# Mini-Keyboard.net
KiCad netlist of a schematic drawn in EasyEDA Pro
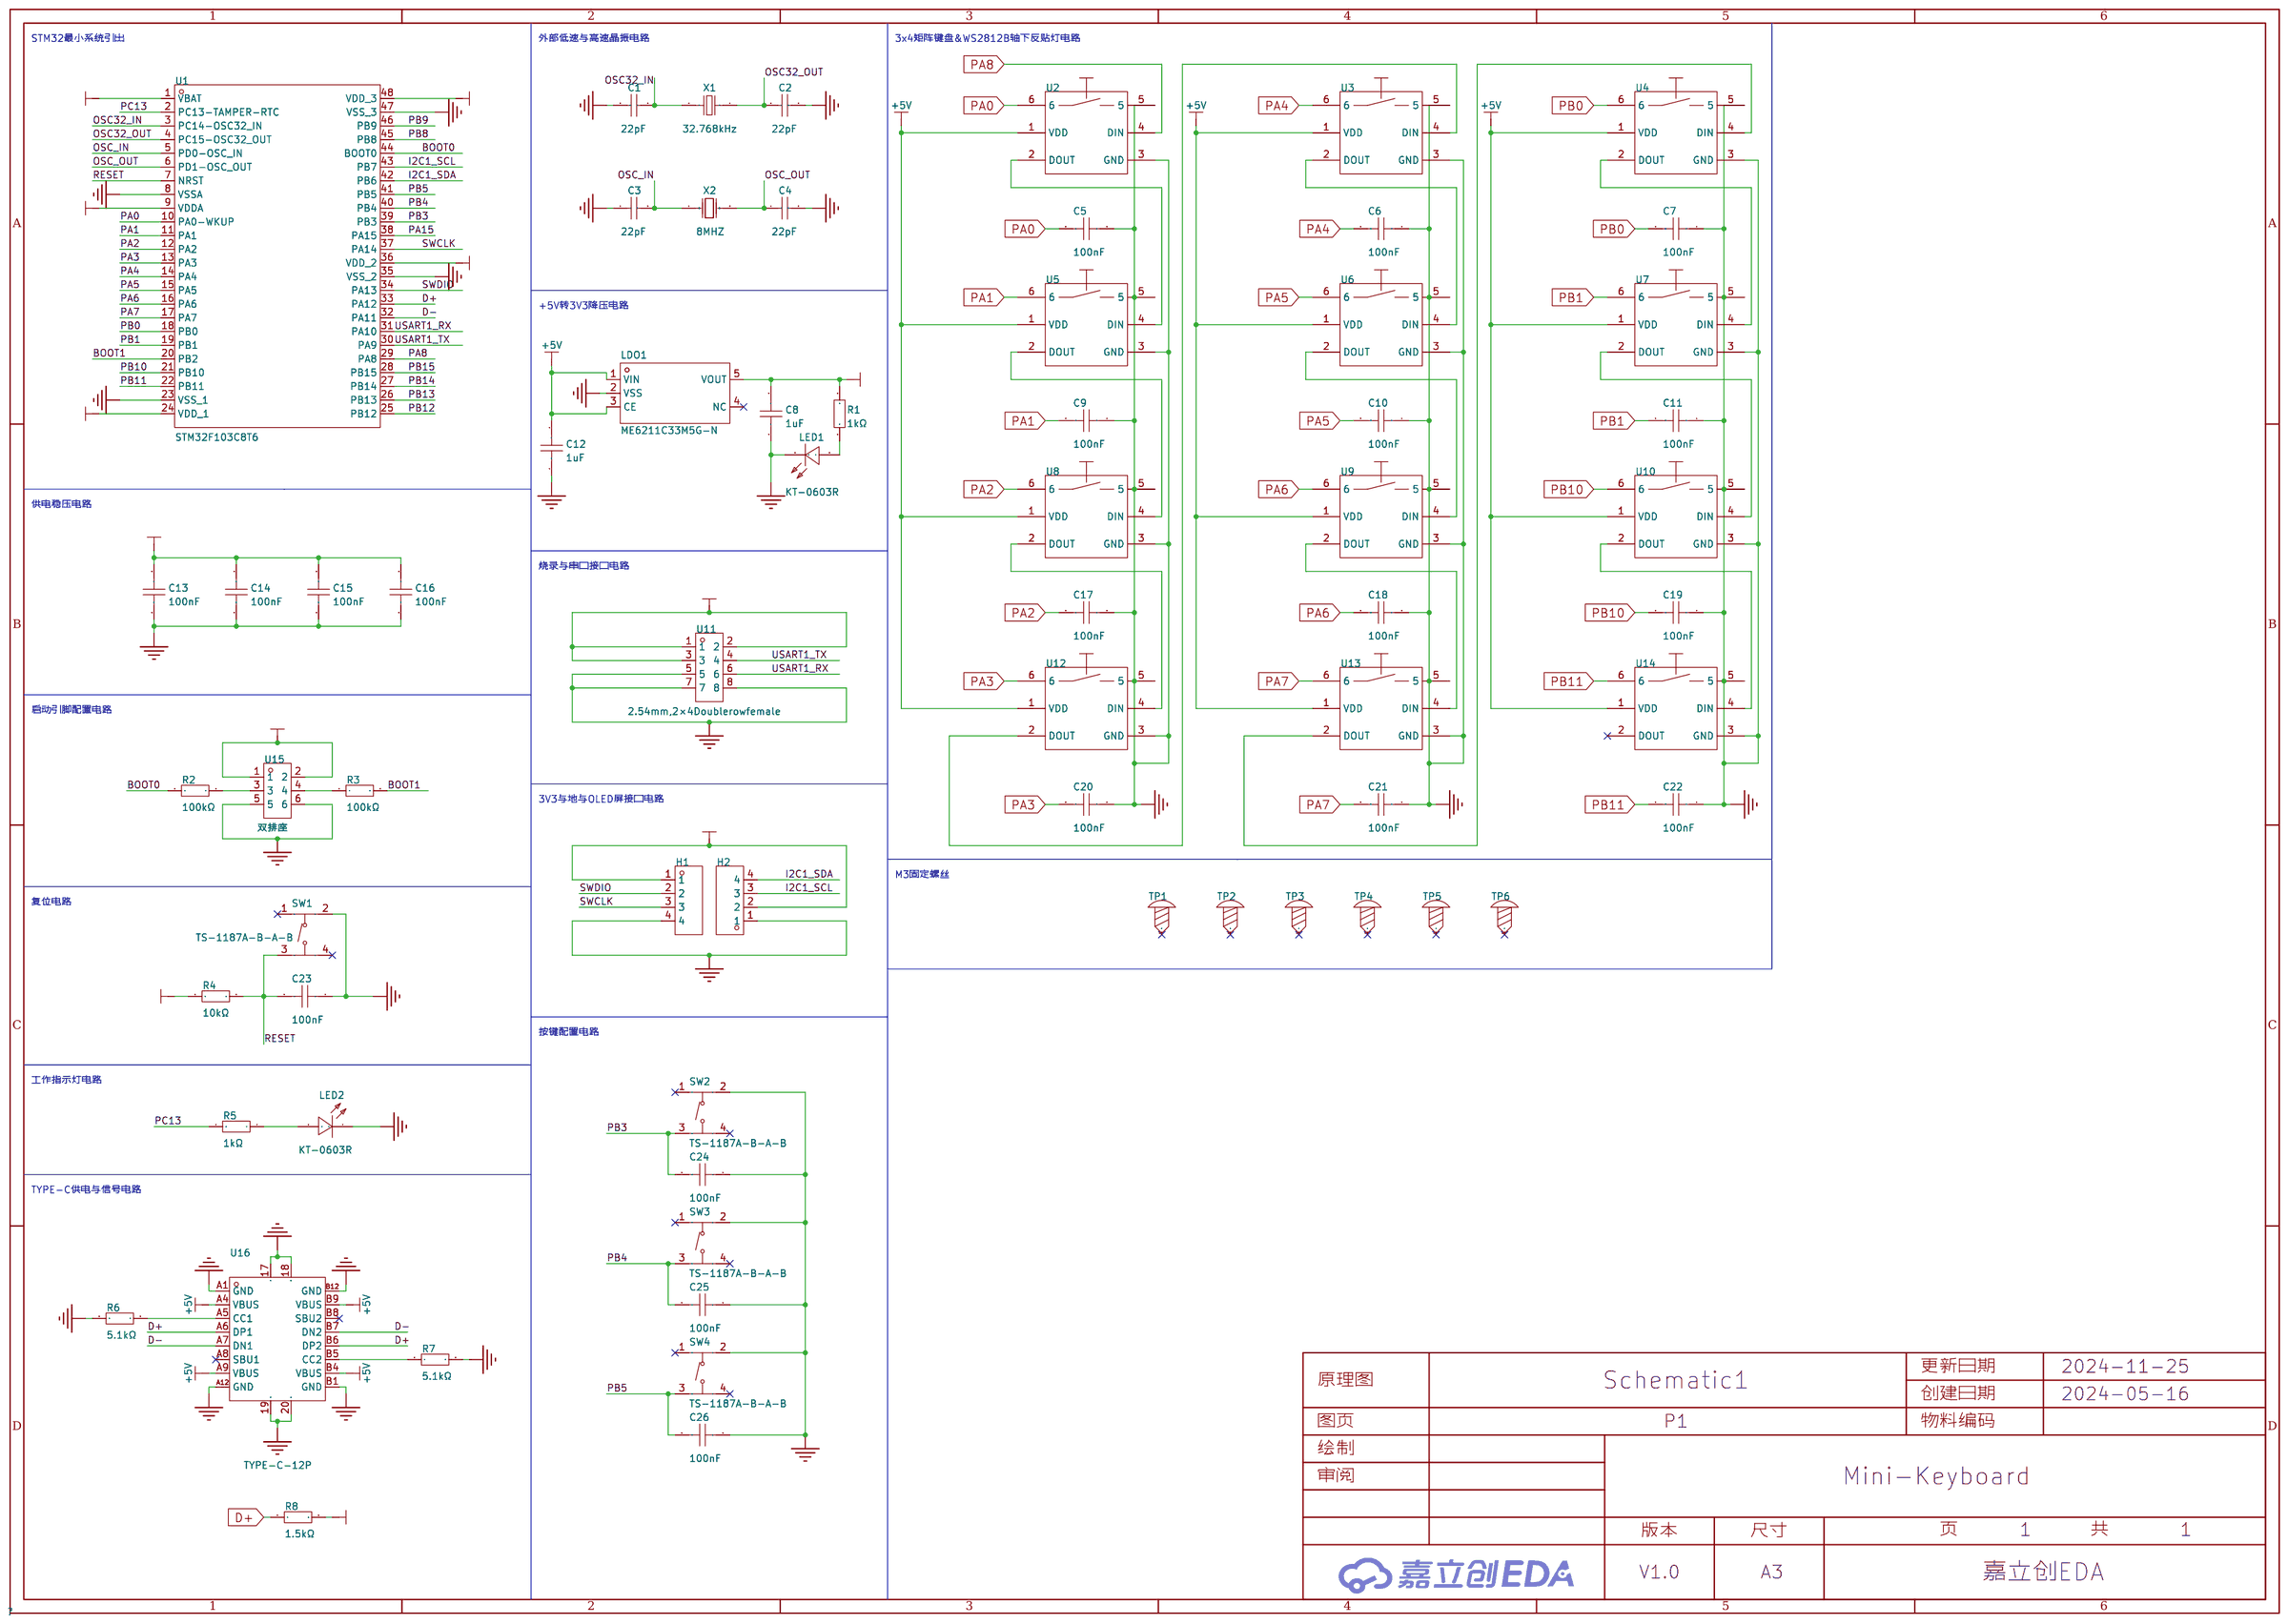
[diagram p0: schematic sheet]

(export (version "E")
  (design (tool "Eeschema 10.0.6"))
  (components
    (comp (ref "C1")
      (value "22pF")
      (footprint "easyedapro:C0603")
      (description "容值:22pF;精度:±5%;额定电压:50V;材质(温度系数):C0G;")
      (fields
        (field (name "Manufacturer Part") "CL10C220JB8NNNC")
        (field (name "Manufacturer") "SAMSUNG(三星)")
      )
      (libsource (lib "easyedapro") (part "CL10C220JB8NNNC"))
    )
    (comp (ref "C2")
      (value "22pF")
      (footprint "easyedapro:C0603")
      (description "容值:22pF;精度:±5%;额定电压:50V;材质(温度系数):C0G;")
      (fields
        (field (name "Manufacturer Part") "CL10C220JB8NNNC")
        (field (name "Manufacturer") "SAMSUNG(三星)")
      )
      (libsource (lib "easyedapro") (part "CL10C220JB8NNNC"))
    )
    (comp (ref "C3")
      (value "22pF")
      (footprint "easyedapro:C0603")
      (description "容值:22pF;精度:±5%;额定电压:50V;材质(温度系数):C0G;")
      (fields
        (field (name "Manufacturer Part") "CL10C220JB8NNNC")
        (field (name "Manufacturer") "SAMSUNG(三星)")
      )
      (libsource (lib "easyedapro") (part "CL10C220JB8NNNC"))
    )
    (comp (ref "C4")
      (value "22pF")
      (footprint "easyedapro:C0603")
      (description "容值:22pF;精度:±5%;额定电压:50V;材质(温度系数):C0G;")
      (fields
        (field (name "Manufacturer Part") "CL10C220JB8NNNC")
        (field (name "Manufacturer") "SAMSUNG(三星)")
      )
      (libsource (lib "easyedapro") (part "CL10C220JB8NNNC"))
    )
    (comp (ref "C5")
      (value "100nF")
      (footprint "easyedapro:C0603")
      (description "容值:100nF;精度:±10%;额定电压:50V;材质(温度系数):X7R;")
      (fields
        (field (name "Manufacturer Part") "CC0603KRX7R9BB104")
        (field (name "Manufacturer") "YAGEO(国巨)")
      )
      (libsource (lib "easyedapro") (part "CC0603KRX7R9BB104"))
    )
    (comp (ref "C6")
      (value "100nF")
      (footprint "easyedapro:C0603")
      (description "容值:100nF;精度:±10%;额定电压:50V;材质(温度系数):X7R;")
      (fields
        (field (name "Manufacturer Part") "CC0603KRX7R9BB104")
        (field (name "Manufacturer") "YAGEO(国巨)")
      )
      (libsource (lib "easyedapro") (part "CC0603KRX7R9BB104"))
    )
    (comp (ref "C7")
      (value "100nF")
      (footprint "easyedapro:C0603")
      (description "容值:100nF;精度:±10%;额定电压:50V;材质(温度系数):X7R;")
      (fields
        (field (name "Manufacturer Part") "CC0603KRX7R9BB104")
        (field (name "Manufacturer") "YAGEO(国巨)")
      )
      (libsource (lib "easyedapro") (part "CC0603KRX7R9BB104"))
    )
    (comp (ref "C8")
      (value "1uF")
      (footprint "easyedapro:C0603")
      (description "容值:1uF;精度:±10%;额定电压:50V;材质(温度系数):X5R;")
      (fields
        (field (name "Manufacturer Part") "CL10A105KB8NNNC")
        (field (name "Manufacturer") "SAMSUNG(三星)")
      )
      (libsource (lib "easyedapro") (part "CL10A105KB8NNNC"))
    )
    (comp (ref "C9")
      (value "100nF")
      (footprint "easyedapro:C0603")
      (description "容值:100nF;精度:±10%;额定电压:50V;材质(温度系数):X7R;")
      (fields
        (field (name "Manufacturer Part") "CC0603KRX7R9BB104")
        (field (name "Manufacturer") "YAGEO(国巨)")
      )
      (libsource (lib "easyedapro") (part "CC0603KRX7R9BB104"))
    )
    (comp (ref "C10")
      (value "100nF")
      (footprint "easyedapro:C0603")
      (description "容值:100nF;精度:±10%;额定电压:50V;材质(温度系数):X7R;")
      (fields
        (field (name "Manufacturer Part") "CC0603KRX7R9BB104")
        (field (name "Manufacturer") "YAGEO(国巨)")
      )
      (libsource (lib "easyedapro") (part "CC0603KRX7R9BB104"))
    )
    (comp (ref "C11")
      (value "100nF")
      (footprint "easyedapro:C0603")
      (description "容值:100nF;精度:±10%;额定电压:50V;材质(温度系数):X7R;")
      (fields
        (field (name "Manufacturer Part") "CC0603KRX7R9BB104")
        (field (name "Manufacturer") "YAGEO(国巨)")
      )
      (libsource (lib "easyedapro") (part "CC0603KRX7R9BB104"))
    )
    (comp (ref "C12")
      (value "1uF")
      (footprint "easyedapro:C0603")
      (description "容值:1uF;精度:±10%;额定电压:50V;材质(温度系数):X5R;")
      (fields
        (field (name "Manufacturer Part") "CL10A105KB8NNNC")
        (field (name "Manufacturer") "SAMSUNG(三星)")
      )
      (libsource (lib "easyedapro") (part "CL10A105KB8NNNC"))
    )
    (comp (ref "C13")
      (value "100nF")
      (footprint "easyedapro:C0603")
      (description "容值:100nF;精度:±10%;额定电压:50V;材质(温度系数):X7R;")
      (fields
        (field (name "Manufacturer Part") "CC0603KRX7R9BB104")
        (field (name "Manufacturer") "YAGEO(国巨)")
      )
      (libsource (lib "easyedapro") (part "CC0603KRX7R9BB104"))
    )
    (comp (ref "C14")
      (value "100nF")
      (footprint "easyedapro:C0603")
      (description "容值:100nF;精度:±10%;额定电压:50V;材质(温度系数):X7R;")
      (fields
        (field (name "Manufacturer Part") "CC0603KRX7R9BB104")
        (field (name "Manufacturer") "YAGEO(国巨)")
      )
      (libsource (lib "easyedapro") (part "CC0603KRX7R9BB104"))
    )
    (comp (ref "C15")
      (value "100nF")
      (footprint "easyedapro:C0603")
      (description "容值:100nF;精度:±10%;额定电压:50V;材质(温度系数):X7R;")
      (fields
        (field (name "Manufacturer Part") "CC0603KRX7R9BB104")
        (field (name "Manufacturer") "YAGEO(国巨)")
      )
      (libsource (lib "easyedapro") (part "CC0603KRX7R9BB104"))
    )
    (comp (ref "C16")
      (value "100nF")
      (footprint "easyedapro:C0603")
      (description "容值:100nF;精度:±10%;额定电压:50V;材质(温度系数):X7R;")
      (fields
        (field (name "Manufacturer Part") "CC0603KRX7R9BB104")
        (field (name "Manufacturer") "YAGEO(国巨)")
      )
      (libsource (lib "easyedapro") (part "CC0603KRX7R9BB104"))
    )
    (comp (ref "C17")
      (value "100nF")
      (footprint "easyedapro:C0603")
      (description "容值:100nF;精度:±10%;额定电压:50V;材质(温度系数):X7R;")
      (fields
        (field (name "Manufacturer Part") "CC0603KRX7R9BB104")
        (field (name "Manufacturer") "YAGEO(国巨)")
      )
      (libsource (lib "easyedapro") (part "CC0603KRX7R9BB104"))
    )
    (comp (ref "C18")
      (value "100nF")
      (footprint "easyedapro:C0603")
      (description "容值:100nF;精度:±10%;额定电压:50V;材质(温度系数):X7R;")
      (fields
        (field (name "Manufacturer Part") "CC0603KRX7R9BB104")
        (field (name "Manufacturer") "YAGEO(国巨)")
      )
      (libsource (lib "easyedapro") (part "CC0603KRX7R9BB104"))
    )
    (comp (ref "C19")
      (value "100nF")
      (footprint "easyedapro:C0603")
      (description "容值:100nF;精度:±10%;额定电压:50V;材质(温度系数):X7R;")
      (fields
        (field (name "Manufacturer Part") "CC0603KRX7R9BB104")
        (field (name "Manufacturer") "YAGEO(国巨)")
      )
      (libsource (lib "easyedapro") (part "CC0603KRX7R9BB104"))
    )
    (comp (ref "C20")
      (value "100nF")
      (footprint "easyedapro:C0603")
      (description "容值:100nF;精度:±10%;额定电压:50V;材质(温度系数):X7R;")
      (fields
        (field (name "Manufacturer Part") "CC0603KRX7R9BB104")
        (field (name "Manufacturer") "YAGEO(国巨)")
      )
      (libsource (lib "easyedapro") (part "CC0603KRX7R9BB104"))
    )
    (comp (ref "C21")
      (value "100nF")
      (footprint "easyedapro:C0603")
      (description "容值:100nF;精度:±10%;额定电压:50V;材质(温度系数):X7R;")
      (fields
        (field (name "Manufacturer Part") "CC0603KRX7R9BB104")
        (field (name "Manufacturer") "YAGEO(国巨)")
      )
      (libsource (lib "easyedapro") (part "CC0603KRX7R9BB104"))
    )
    (comp (ref "C22")
      (value "100nF")
      (footprint "easyedapro:C0603")
      (description "容值:100nF;精度:±10%;额定电压:50V;材质(温度系数):X7R;")
      (fields
        (field (name "Manufacturer Part") "CC0603KRX7R9BB104")
        (field (name "Manufacturer") "YAGEO(国巨)")
      )
      (libsource (lib "easyedapro") (part "CC0603KRX7R9BB104"))
    )
    (comp (ref "C23")
      (value "100nF")
      (footprint "easyedapro:C0603")
      (description "容值:100nF;精度:±10%;额定电压:50V;材质(温度系数):X7R;")
      (fields
        (field (name "Manufacturer Part") "CC0603KRX7R9BB104")
        (field (name "Manufacturer") "YAGEO(国巨)")
      )
      (libsource (lib "easyedapro") (part "CC0603KRX7R9BB104"))
    )
    (comp (ref "C24")
      (value "100nF")
      (footprint "easyedapro:C0603")
      (description "容值:100nF;精度:±10%;额定电压:50V;材质(温度系数):X7R;")
      (fields
        (field (name "Manufacturer Part") "CC0603KRX7R9BB104")
        (field (name "Manufacturer") "YAGEO(国巨)")
      )
      (libsource (lib "easyedapro") (part "CC0603KRX7R9BB104"))
    )
    (comp (ref "C25")
      (value "100nF")
      (footprint "easyedapro:C0603")
      (description "容值:100nF;精度:±10%;额定电压:50V;材质(温度系数):X7R;")
      (fields
        (field (name "Manufacturer Part") "CC0603KRX7R9BB104")
        (field (name "Manufacturer") "YAGEO(国巨)")
      )
      (libsource (lib "easyedapro") (part "CC0603KRX7R9BB104"))
    )
    (comp (ref "C26")
      (value "100nF")
      (footprint "easyedapro:C0603")
      (description "容值:100nF;精度:±10%;额定电压:50V;材质(温度系数):X7R;")
      (fields
        (field (name "Manufacturer Part") "CC0603KRX7R9BB104")
        (field (name "Manufacturer") "YAGEO(国巨)")
      )
      (libsource (lib "easyedapro") (part "CC0603KRX7R9BB104"))
    )
    (comp (ref "H1")
      (value "~")
      (footprint "easyedapro:hdr-th_4p-p2.54-v-f")
      (libsource (lib "easyedapro") (part "2.54-1*4P母"))
    )
    (comp (ref "H2")
      (value "~")
      (footprint "easyedapro:hdr-th_4p-p2.54-v-f")
      (libsource (lib "easyedapro") (part "2.54-1*4P母"))
    )
    (comp (ref "LDO1")
      (value "ME6211C33M5G-N")
      (footprint "easyedapro:SOT-23-5_L3.0-W1.7-P0.95-LS2.8-BL")
      (description "输出类型:固定;最大输入电压:6V;输出电压:3.3V;最大输出电流:500mA;电源纹波抑制比(PSRR):70dB;输出极性:正极;")
      (fields (field (name "Manufacturer") "MICRONE(南京微盟)"))
      (libsource (lib "easyedapro") (part "ME6211C33M5G-N"))
    )
    (comp (ref "LED1")
      (value "KT-0603R")
      (footprint "easyedapro:LED0603-RD")
      (description "发光颜色:红色;功率:-;正向电流:-;主波长:-;二极管配置:-;透镜颜色:-;色温:-;发光角度:-;载带方式:-;工作温度:-40°C~+85°C;")
      (fields (field (name "Manufacturer") "KENTO"))
      (libsource (lib "easyedapro") (part "kt-0603r"))
    )
    (comp (ref "LED2")
      (value "KT-0603R")
      (footprint "easyedapro:LED0603-RD")
      (description "发光颜色:红色;功率:-;正向电流:-;主波长:-;二极管配置:-;透镜颜色:-;色温:-;发光角度:-;载带方式:-;工作温度:-40°C~+85°C;")
      (fields (field (name "Manufacturer") "KENTO"))
      (libsource (lib "easyedapro") (part "kt-0603r"))
    )
    (comp (ref "R1")
      (value "1kΩ")
      (footprint "easyedapro:R0603")
      (description "电阻类型:厚膜电阻;阻值:1kΩ;精度:±1%;功率:100mW;最大工作电压:75V;温度系数:±100ppm/°C;")
      (fields
        (field (name "Manufacturer Part") "0603WAF1001T5E")
        (field (name "Manufacturer") "UNI-ROYAL(厚声)")
      )
      (libsource (lib "easyedapro") (part "0603WAF1001T5E"))
    )
    (comp (ref "R2")
      (value "100kΩ")
      (footprint "easyedapro:R0603")
      (description "电阻类型:厚膜电阻;阻值:100kΩ;精度:±1%;功率:100mW;最大工作电压:75V;温度系数:±100ppm/°C;")
      (fields
        (field (name "Manufacturer Part") "0603WAF1003T5E")
        (field (name "Manufacturer") "UNI-ROYAL(厚声)")
      )
      (libsource (lib "easyedapro") (part "0603WAF1003T5E"))
    )
    (comp (ref "R3")
      (value "100kΩ")
      (footprint "easyedapro:R0603")
      (description "电阻类型:厚膜电阻;阻值:100kΩ;精度:±1%;功率:100mW;最大工作电压:75V;温度系数:±100ppm/°C;")
      (fields
        (field (name "Manufacturer Part") "0603WAF1003T5E")
        (field (name "Manufacturer") "UNI-ROYAL(厚声)")
      )
      (libsource (lib "easyedapro") (part "0603WAF1003T5E"))
    )
    (comp (ref "R4")
      (value "10kΩ")
      (footprint "easyedapro:R0603")
      (description "电阻类型:厚膜电阻;阻值:10kΩ;精度:±1%;功率:100mW;最大工作电压:75V;温度系数:±100ppm/°C;")
      (fields
        (field (name "Manufacturer Part") "0603WAF1002T5E")
        (field (name "Manufacturer") "UNI-ROYAL(厚声)")
      )
      (libsource (lib "easyedapro") (part "0603WAF1002T5E"))
    )
    (comp (ref "R5")
      (value "1kΩ")
      (footprint "easyedapro:R0603")
      (description "电阻类型:厚膜电阻;阻值:1kΩ;精度:±1%;功率:100mW;最大工作电压:75V;温度系数:±100ppm/°C;")
      (fields
        (field (name "Manufacturer Part") "0603WAF1001T5E")
        (field (name "Manufacturer") "UNI-ROYAL(厚声)")
      )
      (libsource (lib "easyedapro") (part "0603WAF1001T5E"))
    )
    (comp (ref "R6")
      (value "5.1kΩ")
      (footprint "easyedapro:R0603")
      (description "电阻类型:厚膜电阻;阻值:5.1kΩ;精度:±1%;功率:100mW;最大工作电压:75V;温度系数:±100ppm/°C;")
      (fields
        (field (name "Manufacturer Part") "0603WAF5101T5E")
        (field (name "Manufacturer") "UNI-ROYAL(厚声)")
      )
      (libsource (lib "easyedapro") (part "0603WAF5101T5E"))
    )
    (comp (ref "R7")
      (value "5.1kΩ")
      (footprint "easyedapro:R0603")
      (description "电阻类型:厚膜电阻;阻值:5.1kΩ;精度:±1%;功率:100mW;最大工作电压:75V;温度系数:±100ppm/°C;")
      (fields
        (field (name "Manufacturer Part") "0603WAF5101T5E")
        (field (name "Manufacturer") "UNI-ROYAL(厚声)")
      )
      (libsource (lib "easyedapro") (part "0603WAF5101T5E"))
    )
    (comp (ref "R8")
      (value "1.5kΩ")
      (footprint "easyedapro:R0603")
      (description "电阻类型:厚膜电阻;阻值:1.5kΩ;精度:±1%;功率:100mW;最大工作电压:75V;温度系数:±100ppm/°C;")
      (fields
        (field (name "Manufacturer Part") "0603WAF1501T5E")
        (field (name "Manufacturer") "UNI-ROYAL(厚声)")
      )
      (libsource (lib "easyedapro") (part "0603WAF1501T5E"))
    )
    (comp (ref "SW1")
      (value "TS-1187A-B-A-B")
      (footprint "easyedapro:SW-SMD_4P-L5.1-W5.1-P3.70-LS6.5-TL-2")
      (fields (field (name "Manufacturer") "XKB Connectivity(中国星坤)"))
      (libsource (lib "easyedapro") (part "TS-1187A-B-A-B"))
    )
    (comp (ref "SW2")
      (value "TS-1187A-B-A-B")
      (footprint "easyedapro:SW-SMD_4P-L5.1-W5.1-P3.70-LS6.5-TL-2")
      (fields (field (name "Manufacturer") "XKB Connectivity(中国星坤)"))
      (libsource (lib "easyedapro") (part "TS-1187A-B-A-B"))
    )
    (comp (ref "SW3")
      (value "TS-1187A-B-A-B")
      (footprint "easyedapro:SW-SMD_4P-L5.1-W5.1-P3.70-LS6.5-TL-2")
      (fields (field (name "Manufacturer") "XKB Connectivity(中国星坤)"))
      (libsource (lib "easyedapro") (part "TS-1187A-B-A-B"))
    )
    (comp (ref "SW4")
      (value "TS-1187A-B-A-B")
      (footprint "easyedapro:SW-SMD_4P-L5.1-W5.1-P3.70-LS6.5-TL-2")
      (fields (field (name "Manufacturer") "XKB Connectivity(中国星坤)"))
      (libsource (lib "easyedapro") (part "TS-1187A-B-A-B"))
    )
    (comp (ref "TP1") (value "~") (footprint "easyedapro:M3螺丝") (libsource (lib "easyedapro") (part "螺丝孔")))
    (comp (ref "TP2") (value "~") (footprint "easyedapro:M3螺丝") (libsource (lib "easyedapro") (part "螺丝孔")))
    (comp (ref "TP3") (value "~") (footprint "easyedapro:M3螺丝") (libsource (lib "easyedapro") (part "螺丝孔")))
    (comp (ref "TP4") (value "~") (footprint "easyedapro:M3螺丝") (libsource (lib "easyedapro") (part "螺丝孔")))
    (comp (ref "TP5") (value "~") (footprint "easyedapro:M3螺丝") (libsource (lib "easyedapro") (part "螺丝孔")))
    (comp (ref "TP6") (value "~") (footprint "easyedapro:M3螺丝") (libsource (lib "easyedapro") (part "螺丝孔")))
    (comp (ref "U1")
      (value "STM32F103C8T6")
      (footprint "easyedapro:LQFP-48_L7.0-W7.0-P0.50-LS9.0-BL")
      (description "CPU内核:ARM-M3;程序存储容量:64KB;RAM总容量:20KB;GPIO端口数量:37;工作电压范围:2V~3.6V;CPU最大主频:72MHz;程序存储器类型:FLASH;")
      (fields (field (name "Manufacturer") "ST(意法半导体)"))
      (libsource (lib "easyedapro") (part "stm32f103c8t6"))
    )
    (comp (ref "U2")
      (value "~")
      (footprint "easyedapro:KAILH_WS2182B_3528 反贴")
      (libsource (lib "easyedapro") (part "KAILH_WS2182B_3528 反贴"))
    )
    (comp (ref "U3")
      (value "~")
      (footprint "easyedapro:KAILH_WS2182B_3528 反贴")
      (libsource (lib "easyedapro") (part "KAILH_WS2182B_3528 反贴"))
    )
    (comp (ref "U4")
      (value "~")
      (footprint "easyedapro:KAILH_WS2182B_3528 反贴")
      (libsource (lib "easyedapro") (part "KAILH_WS2182B_3528 反贴"))
    )
    (comp (ref "U5")
      (value "~")
      (footprint "easyedapro:KAILH_WS2182B_3528 反贴")
      (libsource (lib "easyedapro") (part "KAILH_WS2182B_3528 反贴"))
    )
    (comp (ref "U6")
      (value "~")
      (footprint "easyedapro:KAILH_WS2182B_3528 反贴")
      (libsource (lib "easyedapro") (part "KAILH_WS2182B_3528 反贴"))
    )
    (comp (ref "U7")
      (value "~")
      (footprint "easyedapro:KAILH_WS2182B_3528 反贴")
      (libsource (lib "easyedapro") (part "KAILH_WS2182B_3528 反贴"))
    )
    (comp (ref "U8")
      (value "~")
      (footprint "easyedapro:KAILH_WS2182B_3528 反贴")
      (libsource (lib "easyedapro") (part "KAILH_WS2182B_3528 反贴"))
    )
    (comp (ref "U9")
      (value "~")
      (footprint "easyedapro:KAILH_WS2182B_3528 反贴")
      (libsource (lib "easyedapro") (part "KAILH_WS2182B_3528 反贴"))
    )
    (comp (ref "U10")
      (value "~")
      (footprint "easyedapro:KAILH_WS2182B_3528 反贴")
      (libsource (lib "easyedapro") (part "KAILH_WS2182B_3528 反贴"))
    )
    (comp (ref "U11")
      (value "2.54mm,2×4Doublerowfemale")
      (footprint "easyedapro:HDR-TH_8P-P2.54-V-F-R2-C4-S2.54-1")
      (libsource (lib "easyedapro") (part "2.54MM,2×4DOUBLEROWFEMALE"))
    )
    (comp (ref "U12")
      (value "~")
      (footprint "easyedapro:KAILH_WS2182B_3528 反贴")
      (libsource (lib "easyedapro") (part "KAILH_WS2182B_3528 反贴"))
    )
    (comp (ref "U13")
      (value "~")
      (footprint "easyedapro:KAILH_WS2182B_3528 反贴")
      (libsource (lib "easyedapro") (part "KAILH_WS2182B_3528 反贴"))
    )
    (comp (ref "U14")
      (value "~")
      (footprint "easyedapro:KAILH_WS2182B_3528 反贴")
      (libsource (lib "easyedapro") (part "KAILH_WS2182B_3528 反贴"))
    )
    (comp (ref "U15")
      (value "双排座")
      (footprint "easyedapro:HDR-TH_6P-P2.54-V-F-R2-C3-S2.54")
      (libsource (lib "easyedapro") (part "双排座"))
    )
    (comp (ref "U16")
      (value "TYPE-C-12P")
      (footprint "easyedapro:USB-SMD_TYPE-C16PIN")
      (libsource (lib "easyedapro") (part "TYPE-C-12P"))
    )
    (comp (ref "X1")
      (value "32.768kHz")
      (footprint "easyedapro:CRYSTAL-SMD_L3.2-W1.5-1")
      (description "晶振类型:贴片晶振;频率:32.768kHz;常温频差:±20ppm;外接负载电容:12.5pF;频率稳定度(全温):±20ppm;")
      (fields
        (field (name "Manufacturer Part") "FC31M2-32.768-NTLLLDT")
        (field (name "Manufacturer") "HCI(杭晶)")
      )
      (libsource (lib "easyedapro") (part "FC31M2-32.768-NTLLLDT"))
    )
    (comp (ref "X2")
      (value "8MHZ")
      (footprint "easyedapro:HC-49S_L11.5-W5.0-P4.88")
      (libsource (lib "easyedapro") (part "8MHZ_C9900021358"))
    )
  )
  (nets
    (net (code "1") (name "+5V") (class "Default")
      (node (ref "C12") (pin "2") (pinfunction "2_2") (pintype "unspecified"))
      (node (ref "LDO1") (pin "1") (pinfunction "VIN_1") (pintype "input"))
      (node (ref "LDO1") (pin "3") (pinfunction "CE_3") (pintype "input"))
      (node (ref "U10") (pin "1") (pinfunction "VDD_1") (pintype "input"))
      (node (ref "U12") (pin "1") (pinfunction "VDD_1") (pintype "input"))
      (node (ref "U13") (pin "1") (pinfunction "VDD_1") (pintype "input"))
      (node (ref "U14") (pin "1") (pinfunction "VDD_1") (pintype "input"))
      (node (ref "U16") (pin "A4") (pinfunction "VBUS_A4") (pintype "unspecified"))
      (node (ref "U16") (pin "A9") (pinfunction "VBUS_A9") (pintype "unspecified"))
      (node (ref "U16") (pin "B4") (pinfunction "VBUS_B4") (pintype "unspecified"))
      (node (ref "U16") (pin "B9") (pinfunction "VBUS_B9") (pintype "unspecified"))
      (node (ref "U2") (pin "1") (pinfunction "VDD_1") (pintype "input"))
      (node (ref "U3") (pin "1") (pinfunction "VDD_1") (pintype "input"))
      (node (ref "U4") (pin "1") (pinfunction "VDD_1") (pintype "input"))
      (node (ref "U5") (pin "1") (pinfunction "VDD_1") (pintype "input"))
      (node (ref "U6") (pin "1") (pinfunction "VDD_1") (pintype "input"))
      (node (ref "U7") (pin "1") (pinfunction "VDD_1") (pintype "input"))
      (node (ref "U8") (pin "1") (pinfunction "VDD_1") (pintype "input"))
      (node (ref "U9") (pin "1") (pinfunction "VDD_1") (pintype "input"))
    )
    (net (code "2") (name "/BOOT0") (class "Default")
      (node (ref "R2") (pin "1") (pinfunction "1_1") (pintype "input"))
      (node (ref "U1") (pin "44") (pinfunction "BOOT0_44") (pintype "unspecified"))
    )
    (net (code "3") (name "/BOOT1") (class "Default")
      (node (ref "R3") (pin "2") (pinfunction "2_2") (pintype "input"))
      (node (ref "U1") (pin "20") (pinfunction "PB2_20") (pintype "unspecified"))
    )
    (net (code "4") (name "/D-") (class "Default")
      (node (ref "U1") (pin "32") (pinfunction "PA11_32") (pintype "unspecified"))
      (node (ref "U16") (pin "A7") (pinfunction "DN1_A7") (pintype "unspecified"))
      (node (ref "U16") (pin "B7") (pinfunction "DN2_B7") (pintype "unspecified"))
    )
    (net (code "5") (name "/I2C1_SCL") (class "Default")
      (node (ref "H2") (pin "3") (pinfunction "3_3") (pintype "unspecified"))
      (node (ref "U1") (pin "43") (pinfunction "PB7_43") (pintype "unspecified"))
    )
    (net (code "6") (name "/I2C1_SDA") (class "Default")
      (node (ref "H2") (pin "4") (pinfunction "4_4") (pintype "unspecified"))
      (node (ref "U1") (pin "42") (pinfunction "PB6_42") (pintype "unspecified"))
    )
    (net (code "7") (name "/OSC32_IN") (class "Default")
      (node (ref "C1") (pin "2") (pinfunction "2_2") (pintype "input"))
      (node (ref "U1") (pin "3") (pinfunction "PC14-OSC32_IN_3") (pintype "unspecified"))
      (node (ref "X1") (pin "2") (pinfunction "2_2") (pintype "unspecified"))
    )
    (net (code "8") (name "/OSC32_OUT") (class "Default")
      (node (ref "C2") (pin "2") (pinfunction "2_2") (pintype "input"))
      (node (ref "U1") (pin "4") (pinfunction "PC15-OSC32_OUT_4") (pintype "unspecified"))
      (node (ref "X1") (pin "1") (pinfunction "1_1") (pintype "unspecified"))
    )
    (net (code "9") (name "/OSC_IN") (class "Default")
      (node (ref "C3") (pin "2") (pinfunction "2_2") (pintype "input"))
      (node (ref "U1") (pin "5") (pinfunction "PD0-OSC_IN_5") (pintype "unspecified"))
      (node (ref "X2") (pin "1") (pinfunction "OSC1_1") (pintype "input"))
    )
    (net (code "10") (name "/OSC_OUT") (class "Default")
      (node (ref "C4") (pin "1") (pinfunction "1_1") (pintype "input"))
      (node (ref "U1") (pin "6") (pinfunction "PD1-OSC_OUT_6") (pintype "unspecified"))
      (node (ref "X2") (pin "2") (pinfunction "OSC2_2") (pintype "input"))
    )
    (net (code "11") (name "/PA15") (class "Default")
      (node (ref "U1") (pin "38") (pinfunction "PA15_38") (pintype "unspecified"))
    )
    (net (code "12") (name "/PB3") (class "Default")
      (node (ref "C24") (pin "2") (pinfunction "2_2") (pintype "unspecified"))
      (node (ref "SW2") (pin "3") (pinfunction "C_3") (pintype "unspecified"))
      (node (ref "U1") (pin "39") (pinfunction "PB3_39") (pintype "unspecified"))
    )
    (net (code "13") (name "/PB4") (class "Default")
      (node (ref "C25") (pin "2") (pinfunction "2_2") (pintype "unspecified"))
      (node (ref "SW3") (pin "3") (pinfunction "C_3") (pintype "unspecified"))
      (node (ref "U1") (pin "40") (pinfunction "PB4_40") (pintype "unspecified"))
    )
    (net (code "14") (name "/PB5") (class "Default")
      (node (ref "C26") (pin "2") (pinfunction "2_2") (pintype "unspecified"))
      (node (ref "SW4") (pin "3") (pinfunction "C_3") (pintype "unspecified"))
      (node (ref "U1") (pin "41") (pinfunction "PB5_41") (pintype "unspecified"))
    )
    (net (code "15") (name "/PB8") (class "Default")
      (node (ref "U1") (pin "45") (pinfunction "PB8_45") (pintype "unspecified"))
    )
    (net (code "16") (name "/PB9") (class "Default")
      (node (ref "U1") (pin "46") (pinfunction "PB9_46") (pintype "unspecified"))
    )
    (net (code "17") (name "/PB12") (class "Default")
      (node (ref "U1") (pin "25") (pinfunction "PB12_25") (pintype "unspecified"))
    )
    (net (code "18") (name "/PB13") (class "Default")
      (node (ref "U1") (pin "26") (pinfunction "PB13_26") (pintype "unspecified"))
    )
    (net (code "19") (name "/PB14") (class "Default")
      (node (ref "U1") (pin "27") (pinfunction "PB14_27") (pintype "unspecified"))
    )
    (net (code "20") (name "/PB15") (class "Default")
      (node (ref "U1") (pin "28") (pinfunction "PB15_28") (pintype "unspecified"))
    )
    (net (code "21") (name "/PC13") (class "Default")
      (node (ref "R5") (pin "2") (pinfunction "2_2") (pintype "input"))
      (node (ref "U1") (pin "2") (pinfunction "PC13-TAMPER-RTC_2") (pintype "unspecified"))
    )
    (net (code "22") (name "/RESET") (class "Default")
      (node (ref "C23") (pin "2") (pinfunction "2_2") (pintype "unspecified"))
      (node (ref "R4") (pin "1") (pinfunction "1_1") (pintype "input"))
      (node (ref "SW1") (pin "3") (pinfunction "C_3") (pintype "unspecified"))
      (node (ref "U1") (pin "7") (pinfunction "NRST_7") (pintype "unspecified"))
    )
    (net (code "23") (name "/SWCLK") (class "Default")
      (node (ref "H1") (pin "3") (pinfunction "3_3") (pintype "unspecified"))
      (node (ref "U1") (pin "37") (pinfunction "PA14_37") (pintype "unspecified"))
    )
    (net (code "24") (name "/SWDIO") (class "Default")
      (node (ref "H1") (pin "2") (pinfunction "2_2") (pintype "unspecified"))
      (node (ref "U1") (pin "34") (pinfunction "PA13_34") (pintype "unspecified"))
    )
    (net (code "25") (name "/USART1_RX") (class "Default")
      (node (ref "U1") (pin "31") (pinfunction "PA10_31") (pintype "unspecified"))
      (node (ref "U11") (pin "6") (pinfunction "6_6") (pintype "unspecified"))
    )
    (net (code "26") (name "/USART1_TX") (class "Default")
      (node (ref "U1") (pin "30") (pinfunction "PA9_30") (pintype "unspecified"))
      (node (ref "U11") (pin "4") (pinfunction "4_4") (pintype "unspecified"))
    )
    (net (code "27") (name "3V3") (class "Default")
      (node (ref "C13") (pin "2") (pinfunction "2_2") (pintype "unspecified"))
      (node (ref "C14") (pin "2") (pinfunction "2_2") (pintype "unspecified"))
      (node (ref "C15") (pin "2") (pinfunction "2_2") (pintype "unspecified"))
      (node (ref "C16") (pin "2") (pinfunction "2_2") (pintype "unspecified"))
      (node (ref "C8") (pin "2") (pinfunction "2_2") (pintype "unspecified"))
      (node (ref "H1") (pin "1") (pinfunction "1_1") (pintype "unspecified"))
      (node (ref "H2") (pin "2") (pinfunction "2_2") (pintype "unspecified"))
      (node (ref "LDO1") (pin "5") (pinfunction "VOUT_5") (pintype "input"))
      (node (ref "R1") (pin "2") (pinfunction "2_2") (pintype "input"))
      (node (ref "R4") (pin "2") (pinfunction "2_2") (pintype "input"))
      (node (ref "R8") (pin "2") (pinfunction "2_2") (pintype "input"))
      (node (ref "U1") (pin "1") (pinfunction "VBAT_1") (pintype "unspecified"))
      (node (ref "U1") (pin "24") (pinfunction "VDD_1_24") (pintype "unspecified"))
      (node (ref "U1") (pin "36") (pinfunction "VDD_2_36") (pintype "unspecified"))
      (node (ref "U1") (pin "48") (pinfunction "VDD_3_48") (pintype "unspecified"))
      (node (ref "U1") (pin "9") (pinfunction "VDDA_9") (pintype "unspecified"))
      (node (ref "U11") (pin "1") (pinfunction "1_1") (pintype "unspecified"))
      (node (ref "U11") (pin "2") (pinfunction "2_2") (pintype "unspecified"))
      (node (ref "U11") (pin "3") (pinfunction "3_3") (pintype "unspecified"))
      (node (ref "U15") (pin "1") (pinfunction "1_1") (pintype "unspecified"))
      (node (ref "U15") (pin "2") (pinfunction "2_2") (pintype "unspecified"))
    )
    (net (code "28") (name "D+") (class "Default")
      (node (ref "R8") (pin "1") (pinfunction "1_1") (pintype "input"))
      (node (ref "U1") (pin "33") (pinfunction "PA12_33") (pintype "unspecified"))
      (node (ref "U16") (pin "A6") (pinfunction "DP1_A6") (pintype "unspecified"))
      (node (ref "U16") (pin "B6") (pinfunction "DP2_B6") (pintype "unspecified"))
    )
    (net (code "29") (name "GND") (class "Default")
      (node (ref "C1") (pin "1") (pinfunction "1_1") (pintype "input"))
      (node (ref "C10") (pin "1") (pinfunction "1_1") (pintype "unspecified"))
      (node (ref "C11") (pin "1") (pinfunction "1_1") (pintype "unspecified"))
      (node (ref "C12") (pin "1") (pinfunction "1_1") (pintype "unspecified"))
      (node (ref "C13") (pin "1") (pinfunction "1_1") (pintype "unspecified"))
      (node (ref "C14") (pin "1") (pinfunction "1_1") (pintype "unspecified"))
      (node (ref "C15") (pin "1") (pinfunction "1_1") (pintype "unspecified"))
      (node (ref "C16") (pin "1") (pinfunction "1_1") (pintype "unspecified"))
      (node (ref "C17") (pin "1") (pinfunction "1_1") (pintype "unspecified"))
      (node (ref "C18") (pin "1") (pinfunction "1_1") (pintype "unspecified"))
      (node (ref "C19") (pin "1") (pinfunction "1_1") (pintype "unspecified"))
      (node (ref "C2") (pin "1") (pinfunction "1_1") (pintype "input"))
      (node (ref "C20") (pin "1") (pinfunction "1_1") (pintype "unspecified"))
      (node (ref "C21") (pin "1") (pinfunction "1_1") (pintype "unspecified"))
      (node (ref "C22") (pin "1") (pinfunction "1_1") (pintype "unspecified"))
      (node (ref "C23") (pin "1") (pinfunction "1_1") (pintype "unspecified"))
      (node (ref "C24") (pin "1") (pinfunction "1_1") (pintype "unspecified"))
      (node (ref "C25") (pin "1") (pinfunction "1_1") (pintype "unspecified"))
      (node (ref "C26") (pin "1") (pinfunction "1_1") (pintype "unspecified"))
      (node (ref "C3") (pin "1") (pinfunction "1_1") (pintype "input"))
      (node (ref "C4") (pin "2") (pinfunction "2_2") (pintype "input"))
      (node (ref "C5") (pin "1") (pinfunction "1_1") (pintype "unspecified"))
      (node (ref "C6") (pin "1") (pinfunction "1_1") (pintype "unspecified"))
      (node (ref "C7") (pin "1") (pinfunction "1_1") (pintype "unspecified"))
      (node (ref "C8") (pin "1") (pinfunction "1_1") (pintype "unspecified"))
      (node (ref "C9") (pin "1") (pinfunction "1_1") (pintype "unspecified"))
      (node (ref "H1") (pin "4") (pinfunction "4_4") (pintype "unspecified"))
      (node (ref "H2") (pin "1") (pinfunction "1_1") (pintype "unspecified"))
      (node (ref "LDO1") (pin "2") (pinfunction "VSS_2") (pintype "input"))
      (node (ref "LED1") (pin "1") (pinfunction "K_1") (pintype "unspecified"))
      (node (ref "LED2") (pin "1") (pinfunction "K_1") (pintype "unspecified"))
      (node (ref "R6") (pin "1") (pinfunction "1_1") (pintype "input"))
      (node (ref "R7") (pin "2") (pinfunction "2_2") (pintype "input"))
      (node (ref "SW1") (pin "2") (pinfunction "B_2") (pintype "unspecified"))
      (node (ref "SW2") (pin "2") (pinfunction "B_2") (pintype "unspecified"))
      (node (ref "SW3") (pin "2") (pinfunction "B_2") (pintype "unspecified"))
      (node (ref "SW4") (pin "2") (pinfunction "B_2") (pintype "unspecified"))
      (node (ref "U1") (pin "23") (pinfunction "VSS_1_23") (pintype "unspecified"))
      (node (ref "U1") (pin "35") (pinfunction "VSS_2_35") (pintype "unspecified"))
      (node (ref "U1") (pin "47") (pinfunction "VSS_3_47") (pintype "unspecified"))
      (node (ref "U1") (pin "8") (pinfunction "VSSA_8") (pintype "unspecified"))
      (node (ref "U10") (pin "3") (pinfunction "GND_3") (pintype "input"))
      (node (ref "U10") (pin "5") (pinfunction "5_5") (pintype "input"))
      (node (ref "U11") (pin "5") (pinfunction "5_5") (pintype "unspecified"))
      (node (ref "U11") (pin "7") (pinfunction "7_7") (pintype "unspecified"))
      (node (ref "U11") (pin "8") (pinfunction "8_8") (pintype "unspecified"))
      (node (ref "U12") (pin "3") (pinfunction "GND_3") (pintype "input"))
      (node (ref "U12") (pin "5") (pinfunction "5_5") (pintype "input"))
      (node (ref "U13") (pin "3") (pinfunction "GND_3") (pintype "input"))
      (node (ref "U13") (pin "5") (pinfunction "5_5") (pintype "input"))
      (node (ref "U14") (pin "3") (pinfunction "GND_3") (pintype "input"))
      (node (ref "U14") (pin "5") (pinfunction "5_5") (pintype "input"))
      (node (ref "U15") (pin "5") (pinfunction "5_5") (pintype "unspecified"))
      (node (ref "U15") (pin "6") (pinfunction "6_6") (pintype "unspecified"))
      (node (ref "U16") (pin "17") (pinfunction "17_17") (pintype "unspecified"))
      (node (ref "U16") (pin "18") (pinfunction "18_18") (pintype "unspecified"))
      (node (ref "U16") (pin "19") (pinfunction "19_19") (pintype "unspecified"))
      (node (ref "U16") (pin "20") (pinfunction "20_20") (pintype "unspecified"))
      (node (ref "U16") (pin "A1") (pinfunction "GND_A1") (pintype "unspecified"))
      (node (ref "U16") (pin "A12") (pinfunction "GND_A12") (pintype "unspecified"))
      (node (ref "U16") (pin "B1") (pinfunction "GND_B1") (pintype "unspecified"))
      (node (ref "U16") (pin "B12") (pinfunction "GND_B12") (pintype "unspecified"))
      (node (ref "U2") (pin "3") (pinfunction "GND_3") (pintype "input"))
      (node (ref "U2") (pin "5") (pinfunction "5_5") (pintype "input"))
      (node (ref "U3") (pin "3") (pinfunction "GND_3") (pintype "input"))
      (node (ref "U3") (pin "5") (pinfunction "5_5") (pintype "input"))
      (node (ref "U4") (pin "3") (pinfunction "GND_3") (pintype "input"))
      (node (ref "U4") (pin "5") (pinfunction "5_5") (pintype "input"))
      (node (ref "U5") (pin "3") (pinfunction "GND_3") (pintype "input"))
      (node (ref "U5") (pin "5") (pinfunction "5_5") (pintype "input"))
      (node (ref "U6") (pin "3") (pinfunction "GND_3") (pintype "input"))
      (node (ref "U6") (pin "5") (pinfunction "5_5") (pintype "input"))
      (node (ref "U7") (pin "3") (pinfunction "GND_3") (pintype "input"))
      (node (ref "U7") (pin "5") (pinfunction "5_5") (pintype "input"))
      (node (ref "U8") (pin "3") (pinfunction "GND_3") (pintype "input"))
      (node (ref "U8") (pin "5") (pinfunction "5_5") (pintype "input"))
      (node (ref "U9") (pin "3") (pinfunction "GND_3") (pintype "input"))
      (node (ref "U9") (pin "5") (pinfunction "5_5") (pintype "input"))
    )
    (net (code "30") (name "Net-(LED1-A)") (class "Default")
      (node (ref "LED1") (pin "2") (pinfunction "A_2") (pintype "unspecified"))
      (node (ref "R1") (pin "1") (pinfunction "1_1") (pintype "input"))
    )
    (net (code "31") (name "Net-(LED2-A)") (class "Default")
      (node (ref "LED2") (pin "2") (pinfunction "A_2") (pintype "unspecified"))
      (node (ref "R5") (pin "1") (pinfunction "1_1") (pintype "input"))
    )
    (net (code "32") (name "Net-(R2-Pad2)") (class "Default")
      (node (ref "R2") (pin "2") (pinfunction "2_2") (pintype "input"))
      (node (ref "U15") (pin "3") (pinfunction "3_3") (pintype "unspecified"))
    )
    (net (code "33") (name "Net-(R3-Pad1)") (class "Default")
      (node (ref "R3") (pin "1") (pinfunction "1_1") (pintype "input"))
      (node (ref "U15") (pin "4") (pinfunction "4_4") (pintype "unspecified"))
    )
    (net (code "34") (name "Net-(U2-DOUT)") (class "Default")
      (node (ref "U2") (pin "2") (pinfunction "DOUT_2") (pintype "input"))
      (node (ref "U5") (pin "4") (pinfunction "DIN_4") (pintype "input"))
    )
    (net (code "35") (name "Net-(U3-DOUT)") (class "Default")
      (node (ref "U3") (pin "2") (pinfunction "DOUT_2") (pintype "input"))
      (node (ref "U6") (pin "4") (pinfunction "DIN_4") (pintype "input"))
    )
    (net (code "36") (name "Net-(U4-DOUT)") (class "Default")
      (node (ref "U4") (pin "2") (pinfunction "DOUT_2") (pintype "input"))
      (node (ref "U7") (pin "4") (pinfunction "DIN_4") (pintype "input"))
    )
    (net (code "37") (name "Net-(U5-DOUT)") (class "Default")
      (node (ref "U5") (pin "2") (pinfunction "DOUT_2") (pintype "input"))
      (node (ref "U8") (pin "4") (pinfunction "DIN_4") (pintype "input"))
    )
    (net (code "38") (name "Net-(U6-DOUT)") (class "Default")
      (node (ref "U6") (pin "2") (pinfunction "DOUT_2") (pintype "input"))
      (node (ref "U9") (pin "4") (pinfunction "DIN_4") (pintype "input"))
    )
    (net (code "39") (name "Net-(U10-DIN)") (class "Default")
      (node (ref "U10") (pin "4") (pinfunction "DIN_4") (pintype "input"))
      (node (ref "U7") (pin "2") (pinfunction "DOUT_2") (pintype "input"))
    )
    (net (code "40") (name "Net-(U10-DOUT)") (class "Default")
      (node (ref "U10") (pin "2") (pinfunction "DOUT_2") (pintype "input"))
      (node (ref "U14") (pin "4") (pinfunction "DIN_4") (pintype "input"))
    )
    (net (code "41") (name "Net-(U12-DIN)") (class "Default")
      (node (ref "U12") (pin "4") (pinfunction "DIN_4") (pintype "input"))
      (node (ref "U8") (pin "2") (pinfunction "DOUT_2") (pintype "input"))
    )
    (net (code "42") (name "Net-(U12-DOUT)") (class "Default")
      (node (ref "U12") (pin "2") (pinfunction "DOUT_2") (pintype "input"))
      (node (ref "U3") (pin "4") (pinfunction "DIN_4") (pintype "input"))
    )
    (net (code "43") (name "Net-(U13-DIN)") (class "Default")
      (node (ref "U13") (pin "4") (pinfunction "DIN_4") (pintype "input"))
      (node (ref "U9") (pin "2") (pinfunction "DOUT_2") (pintype "input"))
    )
    (net (code "44") (name "Net-(U13-DOUT)") (class "Default")
      (node (ref "U13") (pin "2") (pinfunction "DOUT_2") (pintype "input"))
      (node (ref "U4") (pin "4") (pinfunction "DIN_4") (pintype "input"))
    )
    (net (code "45") (name "Net-(U16-CC1)") (class "Default")
      (node (ref "R6") (pin "2") (pinfunction "2_2") (pintype "input"))
      (node (ref "U16") (pin "A5") (pinfunction "CC1_A5") (pintype "unspecified"))
    )
    (net (code "46") (name "Net-(U16-CC2)") (class "Default")
      (node (ref "R7") (pin "1") (pinfunction "1_1") (pintype "input"))
      (node (ref "U16") (pin "B5") (pinfunction "CC2_B5") (pintype "unspecified"))
    )
    (net (code "47") (name "PA0") (class "Default")
      (node (ref "C5") (pin "2") (pinfunction "2_2") (pintype "unspecified"))
      (node (ref "U1") (pin "10") (pinfunction "PA0-WKUP_10") (pintype "unspecified"))
      (node (ref "U2") (pin "6") (pinfunction "6_6") (pintype "input"))
    )
    (net (code "48") (name "PA1") (class "Default")
      (node (ref "C9") (pin "2") (pinfunction "2_2") (pintype "unspecified"))
      (node (ref "U1") (pin "11") (pinfunction "PA1_11") (pintype "unspecified"))
      (node (ref "U5") (pin "6") (pinfunction "6_6") (pintype "input"))
    )
    (net (code "49") (name "PA2") (class "Default")
      (node (ref "C17") (pin "2") (pinfunction "2_2") (pintype "unspecified"))
      (node (ref "U1") (pin "12") (pinfunction "PA2_12") (pintype "unspecified"))
      (node (ref "U8") (pin "6") (pinfunction "6_6") (pintype "input"))
    )
    (net (code "50") (name "PA3") (class "Default")
      (node (ref "C20") (pin "2") (pinfunction "2_2") (pintype "unspecified"))
      (node (ref "U1") (pin "13") (pinfunction "PA3_13") (pintype "unspecified"))
      (node (ref "U12") (pin "6") (pinfunction "6_6") (pintype "input"))
    )
    (net (code "51") (name "PA4") (class "Default")
      (node (ref "C6") (pin "2") (pinfunction "2_2") (pintype "unspecified"))
      (node (ref "U1") (pin "14") (pinfunction "PA4_14") (pintype "unspecified"))
      (node (ref "U3") (pin "6") (pinfunction "6_6") (pintype "input"))
    )
    (net (code "52") (name "PA5") (class "Default")
      (node (ref "C10") (pin "2") (pinfunction "2_2") (pintype "unspecified"))
      (node (ref "U1") (pin "15") (pinfunction "PA5_15") (pintype "unspecified"))
      (node (ref "U6") (pin "6") (pinfunction "6_6") (pintype "input"))
    )
    (net (code "53") (name "PA6") (class "Default")
      (node (ref "C18") (pin "2") (pinfunction "2_2") (pintype "unspecified"))
      (node (ref "U1") (pin "16") (pinfunction "PA6_16") (pintype "unspecified"))
      (node (ref "U9") (pin "6") (pinfunction "6_6") (pintype "input"))
    )
    (net (code "54") (name "PA7") (class "Default")
      (node (ref "C21") (pin "2") (pinfunction "2_2") (pintype "unspecified"))
      (node (ref "U1") (pin "17") (pinfunction "PA7_17") (pintype "unspecified"))
      (node (ref "U13") (pin "6") (pinfunction "6_6") (pintype "input"))
    )
    (net (code "55") (name "PA8") (class "Default")
      (node (ref "U1") (pin "29") (pinfunction "PA8_29") (pintype "unspecified"))
      (node (ref "U2") (pin "4") (pinfunction "DIN_4") (pintype "input"))
    )
    (net (code "56") (name "PB0") (class "Default")
      (node (ref "C7") (pin "2") (pinfunction "2_2") (pintype "unspecified"))
      (node (ref "U1") (pin "18") (pinfunction "PB0_18") (pintype "unspecified"))
      (node (ref "U4") (pin "6") (pinfunction "6_6") (pintype "input"))
    )
    (net (code "57") (name "PB1") (class "Default")
      (node (ref "C11") (pin "2") (pinfunction "2_2") (pintype "unspecified"))
      (node (ref "U1") (pin "19") (pinfunction "PB1_19") (pintype "unspecified"))
      (node (ref "U7") (pin "6") (pinfunction "6_6") (pintype "input"))
    )
    (net (code "58") (name "PB10") (class "Default")
      (node (ref "C19") (pin "2") (pinfunction "2_2") (pintype "unspecified"))
      (node (ref "U1") (pin "21") (pinfunction "PB10_21") (pintype "unspecified"))
      (node (ref "U10") (pin "6") (pinfunction "6_6") (pintype "input"))
    )
    (net (code "59") (name "PB11") (class "Default")
      (node (ref "C22") (pin "2") (pinfunction "2_2") (pintype "unspecified"))
      (node (ref "U1") (pin "22") (pinfunction "PB11_22") (pintype "unspecified"))
      (node (ref "U14") (pin "6") (pinfunction "6_6") (pintype "input"))
    )
    (net (code "60") (name "unconnected-(LDO1-NC-Pad4)") (class "Default")
      (node (ref "LDO1") (pin "4") (pinfunction "NC_4") (pintype "input+no_connect"))
    )
    (net (code "61") (name "unconnected-(SW1-A-Pad1)") (class "Default")
      (node (ref "SW1") (pin "1") (pinfunction "A_1") (pintype "unspecified+no_connect"))
    )
    (net (code "62") (name "unconnected-(SW1-D-Pad4)") (class "Default")
      (node (ref "SW1") (pin "4") (pinfunction "D_4") (pintype "unspecified+no_connect"))
    )
    (net (code "63") (name "unconnected-(SW2-A-Pad1)") (class "Default")
      (node (ref "SW2") (pin "1") (pinfunction "A_1") (pintype "unspecified+no_connect"))
    )
    (net (code "64") (name "unconnected-(SW2-D-Pad4)") (class "Default")
      (node (ref "SW2") (pin "4") (pinfunction "D_4") (pintype "unspecified+no_connect"))
    )
    (net (code "65") (name "unconnected-(SW3-A-Pad1)") (class "Default")
      (node (ref "SW3") (pin "1") (pinfunction "A_1") (pintype "unspecified+no_connect"))
    )
    (net (code "66") (name "unconnected-(SW3-D-Pad4)") (class "Default")
      (node (ref "SW3") (pin "4") (pinfunction "D_4") (pintype "unspecified+no_connect"))
    )
    (net (code "67") (name "unconnected-(SW4-A-Pad1)") (class "Default")
      (node (ref "SW4") (pin "1") (pinfunction "A_1") (pintype "unspecified+no_connect"))
    )
    (net (code "68") (name "unconnected-(SW4-D-Pad4)") (class "Default")
      (node (ref "SW4") (pin "4") (pinfunction "D_4") (pintype "unspecified+no_connect"))
    )
    (net (code "69") (name "unconnected-(TP1-Pad1)") (class "Default")
      (node (ref "TP1") (pin "1") (pinfunction "1_1") (pintype "input+no_connect"))
    )
    (net (code "70") (name "unconnected-(TP2-Pad1)") (class "Default")
      (node (ref "TP2") (pin "1") (pinfunction "1_1") (pintype "input+no_connect"))
    )
    (net (code "71") (name "unconnected-(TP3-Pad1)") (class "Default")
      (node (ref "TP3") (pin "1") (pinfunction "1_1") (pintype "input+no_connect"))
    )
    (net (code "72") (name "unconnected-(TP4-Pad1)") (class "Default")
      (node (ref "TP4") (pin "1") (pinfunction "1_1") (pintype "input+no_connect"))
    )
    (net (code "73") (name "unconnected-(TP5-Pad1)") (class "Default")
      (node (ref "TP5") (pin "1") (pinfunction "1_1") (pintype "input+no_connect"))
    )
    (net (code "74") (name "unconnected-(TP6-Pad1)") (class "Default")
      (node (ref "TP6") (pin "1") (pinfunction "1_1") (pintype "input+no_connect"))
    )
    (net (code "75") (name "unconnected-(U14-DOUT-Pad2)") (class "Default")
      (node (ref "U14") (pin "2") (pinfunction "DOUT_2") (pintype "input+no_connect"))
    )
    (net (code "76") (name "unconnected-(U16-SBU1-PadA8)") (class "Default")
      (node (ref "U16") (pin "A8") (pinfunction "SBU1_A8") (pintype "unspecified+no_connect"))
    )
    (net (code "77") (name "unconnected-(U16-SBU2-PadB8)") (class "Default")
      (node (ref "U16") (pin "B8") (pinfunction "SBU2_B8") (pintype "unspecified+no_connect"))
    )
  )
)
